# infnoise_edgecon.net
KiCad netlist of a schematic drawn in EAGLE
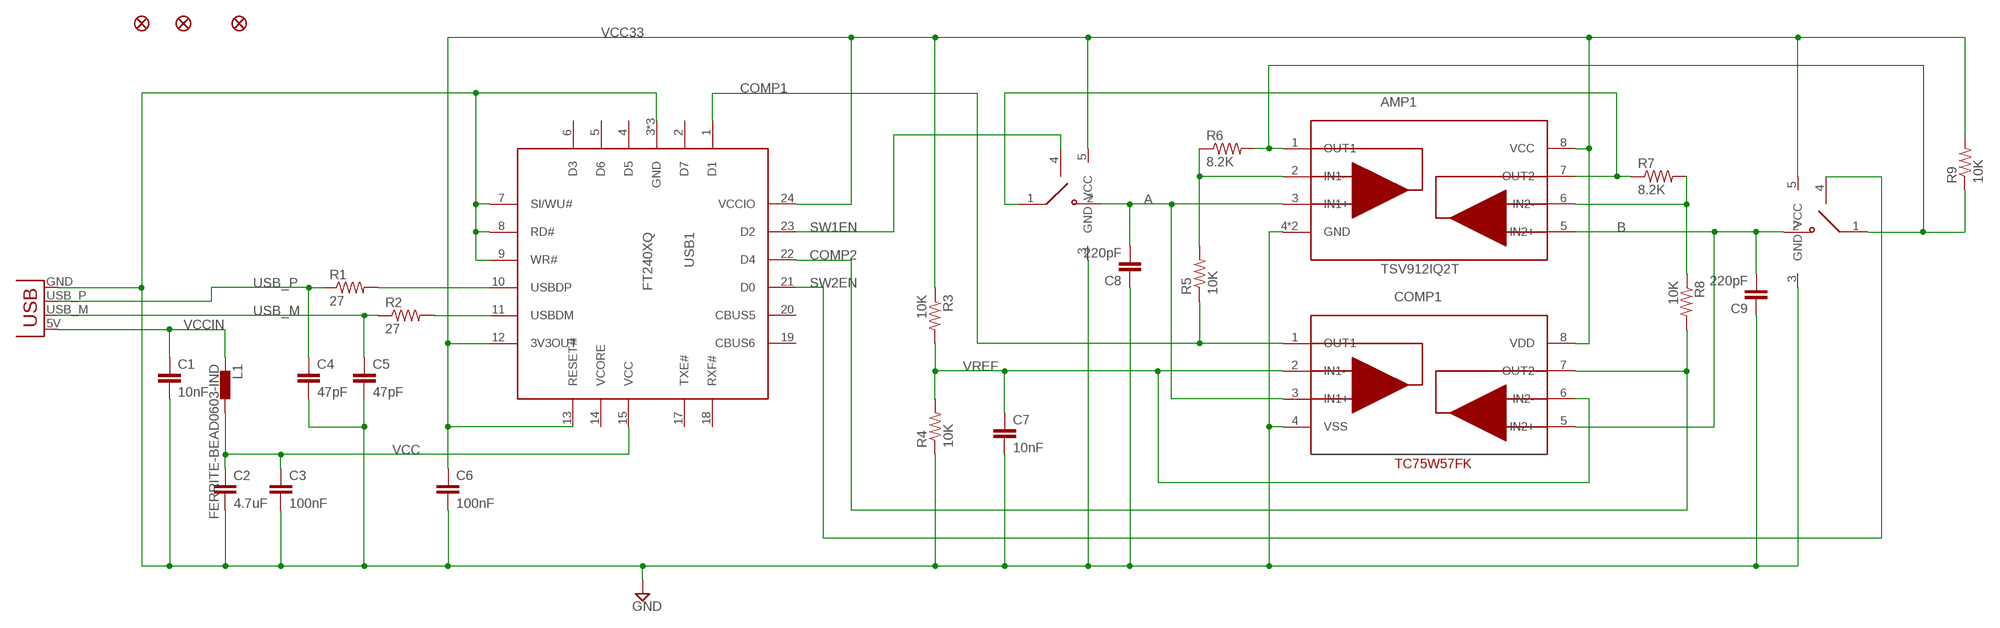
[diagram p0: schematic, sheet 1]

(export (version "E")
  (design (tool "Eeschema 10.0.6"))
  (components
    (comp (ref "AMP1")
      (value "TSV912IQ2T")
      (footprint "eagle-import:DFN8-2X3")
      (libsource (lib "eagle-import") (part "TSV912IQ2T"))
    )
    (comp (ref "C1")
      (value "10nF")
      (footprint "eagle-import:0603-CAP")
      (libsource (lib "eagle-import") (part "CAP0603-CAP"))
    )
    (comp (ref "C2")
      (value "4.7uF")
      (footprint "eagle-import:0603-CAP")
      (libsource (lib "eagle-import") (part "CAP0603-CAP"))
    )
    (comp (ref "C3")
      (value "100nF")
      (footprint "eagle-import:0603-CAP")
      (libsource (lib "eagle-import") (part "CAP0603-CAP"))
    )
    (comp (ref "C4")
      (value "47pF")
      (footprint "eagle-import:0603-CAP")
      (libsource (lib "eagle-import") (part "CAP0603-CAP"))
    )
    (comp (ref "C5")
      (value "47pF")
      (footprint "eagle-import:0603-CAP")
      (libsource (lib "eagle-import") (part "CAP0603-CAP"))
    )
    (comp (ref "C6")
      (value "100nF")
      (footprint "eagle-import:0603-CAP")
      (libsource (lib "eagle-import") (part "CAP0603-CAP"))
    )
    (comp (ref "C7")
      (value "10nF")
      (footprint "eagle-import:0603-CAP")
      (libsource (lib "eagle-import") (part "CAP0603-CAP"))
    )
    (comp (ref "C8")
      (value "220pF")
      (footprint "eagle-import:0603-CAP")
      (libsource (lib "eagle-import") (part "CAP0603-CAP"))
    )
    (comp (ref "C9")
      (value "220pF")
      (footprint "eagle-import:0603-CAP")
      (libsource (lib "eagle-import") (part "CAP0603-CAP"))
    )
    (comp (ref "COMP1")
      (value "TC75W57FK")
      (footprint "eagle-import:SSOP8-P-0.50A")
      (libsource (lib "eagle-import") (part "TC75W57FK"))
    )
    (comp (ref "FID1")
      (value "FIDUCIALUFIDUCIAL")
      (footprint "eagle-import:MICRO-FIDUCIAL")
      (libsource (lib "eagle-import") (part "FIDUCIALUFIDUCIAL"))
    )
    (comp (ref "FID2")
      (value "FIDUCIALUFIDUCIAL")
      (footprint "eagle-import:MICRO-FIDUCIAL")
      (libsource (lib "eagle-import") (part "FIDUCIALUFIDUCIAL"))
    )
    (comp (ref "FID3")
      (value "FIDUCIALUFIDUCIAL")
      (footprint "eagle-import:MICRO-FIDUCIAL")
      (libsource (lib "eagle-import") (part "FIDUCIALUFIDUCIAL"))
    )
    (comp (ref "L1")
      (value "FERRITE-BEAD0603-IND")
      (footprint "eagle-import:0603-IND")
      (libsource (lib "eagle-import") (part "FERRITE-BEAD0603-IND"))
    )
    (comp (ref "R1")
      (value "27")
      (footprint "eagle-import:0603-RES")
      (libsource (lib "eagle-import") (part "RESISTOR0603-RES"))
    )
    (comp (ref "R2")
      (value "27")
      (footprint "eagle-import:0603-RES")
      (libsource (lib "eagle-import") (part "RESISTOR0603-RES"))
    )
    (comp (ref "R3")
      (value "10K")
      (footprint "eagle-import:0603-RES")
      (libsource (lib "eagle-import") (part "RESISTOR0603-RES"))
    )
    (comp (ref "R4")
      (value "10K")
      (footprint "eagle-import:0603-RES")
      (libsource (lib "eagle-import") (part "RESISTOR0603-RES"))
    )
    (comp (ref "R5")
      (value "10K")
      (footprint "eagle-import:0603-RES")
      (libsource (lib "eagle-import") (part "RESISTOR0603-RES"))
    )
    (comp (ref "R6")
      (value "8.2K")
      (footprint "eagle-import:0603-RES")
      (libsource (lib "eagle-import") (part "RESISTOR0603-RES"))
    )
    (comp (ref "R7")
      (value "8.2K")
      (footprint "eagle-import:0603-RES")
      (libsource (lib "eagle-import") (part "RESISTOR0603-RES"))
    )
    (comp (ref "R8")
      (value "10K")
      (footprint "eagle-import:0603-RES")
      (libsource (lib "eagle-import") (part "RESISTOR0603-RES"))
    )
    (comp (ref "R9")
      (value "10K")
      (footprint "eagle-import:0603-RES")
      (libsource (lib "eagle-import") (part "RESISTOR0603-RES"))
    )
    (comp (ref "SW1")
      (value "MC74VHC1G66DFT1G")
      (footprint "eagle-import:SC70-5L")
      (libsource (lib "eagle-import") (part "MC74VHC1G66DFT1G"))
    )
    (comp (ref "SW2")
      (value "MC74VHC1G66DFT1G")
      (footprint "eagle-import:SC70-5L")
      (libsource (lib "eagle-import") (part "MC74VHC1G66DFT1G"))
    )
    (comp (ref "USB1")
      (value "FT240XQ")
      (footprint "eagle-import:QFN24-4X4")
      (libsource (lib "eagle-import") (part "FT240XQ"))
    )
    (comp (ref "X1")
      (value "USB")
      (footprint "eagle-import:USB-A-PCB")
      (libsource (lib "eagle-import") (part "USB"))
    )
  )
  (nets
    (net (code "1") (name "/A") (class "Default")
      (node (ref "AMP1") (pin "3") (pinfunction "IN1+_3") (pintype "bidirectional"))
      (node (ref "C8") (pin "2") (pinfunction "2_2") (pintype "passive"))
      (node (ref "COMP1") (pin "3") (pinfunction "IN1+_3") (pintype "bidirectional"))
      (node (ref "SW1") (pin "2") (pinfunction "NO_2") (pintype "bidirectional"))
    )
    (net (code "2") (name "/B") (class "Default")
      (node (ref "AMP1") (pin "5") (pinfunction "IN2+_5") (pintype "bidirectional"))
      (node (ref "C9") (pin "2") (pinfunction "2_2") (pintype "passive"))
      (node (ref "COMP1") (pin "5") (pinfunction "IN2+_5") (pintype "bidirectional"))
      (node (ref "SW2") (pin "2") (pinfunction "NO_2") (pintype "bidirectional"))
    )
    (net (code "3") (name "/COMP1") (class "Default")
      (node (ref "COMP1") (pin "1") (pinfunction "OUT1_1") (pintype "bidirectional"))
      (node (ref "R5") (pin "1") (pinfunction "1_1") (pintype "passive"))
      (node (ref "USB1") (pin "1") (pinfunction "D1_1") (pintype "bidirectional"))
    )
    (net (code "4") (name "/COMP2") (class "Default")
      (node (ref "COMP1") (pin "7") (pinfunction "OUT2_7") (pintype "bidirectional"))
      (node (ref "R8") (pin "2") (pinfunction "2_2") (pintype "passive"))
      (node (ref "USB1") (pin "22") (pinfunction "D4_22") (pintype "bidirectional"))
    )
    (net (code "5") (name "/SW1EN") (class "Default")
      (node (ref "SW1") (pin "4") (pinfunction "IN_4") (pintype "bidirectional"))
      (node (ref "USB1") (pin "23") (pinfunction "D2_23") (pintype "bidirectional"))
    )
    (net (code "6") (name "/SW2EN") (class "Default")
      (node (ref "SW2") (pin "4") (pinfunction "IN_4") (pintype "bidirectional"))
      (node (ref "USB1") (pin "21") (pinfunction "D0_21") (pintype "bidirectional"))
    )
    (net (code "7") (name "/USB_M") (class "Default")
      (node (ref "C5") (pin "1") (pinfunction "1_1") (pintype "passive"))
      (node (ref "R2") (pin "1") (pinfunction "1_1") (pintype "passive"))
      (node (ref "X1") (pin "USB_M") (pinfunction "D-_USB_M") (pintype "bidirectional"))
    )
    (net (code "8") (name "/USB_P") (class "Default")
      (node (ref "C4") (pin "1") (pinfunction "1_1") (pintype "passive"))
      (node (ref "R1") (pin "1") (pinfunction "1_1") (pintype "passive"))
      (node (ref "X1") (pin "USB_P") (pinfunction "D+_USB_P") (pintype "bidirectional"))
    )
    (net (code "9") (name "/VCC") (class "Default")
      (node (ref "C2") (pin "1") (pinfunction "1_1") (pintype "passive"))
      (node (ref "C3") (pin "1") (pinfunction "1_1") (pintype "passive"))
      (node (ref "L1") (pin "2") (pinfunction "2_2") (pintype "passive"))
      (node (ref "USB1") (pin "15") (pinfunction "VCC_15") (pintype "bidirectional"))
    )
    (net (code "10") (name "/VCC33") (class "Default")
      (node (ref "AMP1") (pin "8") (pinfunction "VCC_8") (pintype "bidirectional"))
      (node (ref "C6") (pin "1") (pinfunction "1_1") (pintype "passive"))
      (node (ref "COMP1") (pin "8") (pinfunction "VDD_8") (pintype "bidirectional"))
      (node (ref "R3") (pin "1") (pinfunction "1_1") (pintype "passive"))
      (node (ref "R9") (pin "2") (pinfunction "2_2") (pintype "passive"))
      (node (ref "SW1") (pin "5") (pinfunction "VCC_5") (pintype "bidirectional"))
      (node (ref "SW2") (pin "5") (pinfunction "VCC_5") (pintype "bidirectional"))
      (node (ref "USB1") (pin "12") (pinfunction "3V3OUT_12") (pintype "bidirectional"))
      (node (ref "USB1") (pin "13") (pinfunction "RESET#_13") (pintype "bidirectional"))
      (node (ref "USB1") (pin "24") (pinfunction "VCCIO_24") (pintype "bidirectional"))
    )
    (net (code "11") (name "/VCCIN") (class "Default")
      (node (ref "C1") (pin "1") (pinfunction "1_1") (pintype "passive"))
      (node (ref "L1") (pin "1") (pinfunction "1_1") (pintype "passive"))
      (node (ref "X1") (pin "5V") (pinfunction "VCC_5V") (pintype "bidirectional"))
    )
    (net (code "12") (name "/VREF") (class "Default")
      (node (ref "C7") (pin "1") (pinfunction "1_1") (pintype "passive"))
      (node (ref "COMP1") (pin "2") (pinfunction "IN1-_2") (pintype "bidirectional"))
      (node (ref "COMP1") (pin "6") (pinfunction "IN2-_6") (pintype "bidirectional"))
      (node (ref "R3") (pin "2") (pinfunction "2_2") (pintype "passive"))
      (node (ref "R4") (pin "2") (pinfunction "2_2") (pintype "passive"))
    )
    (net (code "13") (name "GND") (class "Default")
      (node (ref "AMP1") (pin "4") (pinfunction "GND_4") (pintype "bidirectional"))
      (node (ref "AMP1") (pin "EXP") (pinfunction "GND_EXP") (pintype "bidirectional"))
      (node (ref "C1") (pin "2") (pinfunction "2_2") (pintype "passive"))
      (node (ref "C2") (pin "2") (pinfunction "2_2") (pintype "passive"))
      (node (ref "C3") (pin "2") (pinfunction "2_2") (pintype "passive"))
      (node (ref "C4") (pin "2") (pinfunction "2_2") (pintype "passive"))
      (node (ref "C5") (pin "2") (pinfunction "2_2") (pintype "passive"))
      (node (ref "C6") (pin "2") (pinfunction "2_2") (pintype "passive"))
      (node (ref "C7") (pin "2") (pinfunction "2_2") (pintype "passive"))
      (node (ref "C8") (pin "1") (pinfunction "1_1") (pintype "passive"))
      (node (ref "C9") (pin "1") (pinfunction "1_1") (pintype "passive"))
      (node (ref "COMP1") (pin "4") (pinfunction "VSS_4") (pintype "bidirectional"))
      (node (ref "R4") (pin "1") (pinfunction "1_1") (pintype "passive"))
      (node (ref "SW1") (pin "3") (pinfunction "GND_3") (pintype "bidirectional"))
      (node (ref "SW2") (pin "3") (pinfunction "GND_3") (pintype "bidirectional"))
      (node (ref "USB1") (pin "16") (pinfunction "GND_16") (pintype "bidirectional"))
      (node (ref "USB1") (pin "3") (pinfunction "GND_3") (pintype "bidirectional"))
      (node (ref "USB1") (pin "7") (pinfunction "SI/WU#_7") (pintype "bidirectional"))
      (node (ref "USB1") (pin "8") (pinfunction "RD#_8") (pintype "bidirectional"))
      (node (ref "USB1") (pin "9") (pinfunction "WR#_9") (pintype "bidirectional"))
      (node (ref "USB1") (pin "EXP") (pinfunction "GND_EXP") (pintype "bidirectional"))
      (node (ref "X1") (pin "GND") (pinfunction "GND_GND") (pintype "bidirectional"))
    )
    (net (code "14") (name "Net-(AMP1-IN1-)") (class "Default")
      (node (ref "AMP1") (pin "2") (pinfunction "IN1-_2") (pintype "bidirectional"))
      (node (ref "R5") (pin "2") (pinfunction "2_2") (pintype "passive"))
      (node (ref "R6") (pin "1") (pinfunction "1_1") (pintype "passive"))
    )
    (net (code "15") (name "Net-(AMP1-IN2-)") (class "Default")
      (node (ref "AMP1") (pin "6") (pinfunction "IN2-_6") (pintype "bidirectional"))
      (node (ref "R7") (pin "2") (pinfunction "2_2") (pintype "passive"))
      (node (ref "R8") (pin "1") (pinfunction "1_1") (pintype "passive"))
    )
    (net (code "16") (name "Net-(AMP1-OUT1)") (class "Default")
      (node (ref "AMP1") (pin "1") (pinfunction "OUT1_1") (pintype "bidirectional"))
      (node (ref "R6") (pin "2") (pinfunction "2_2") (pintype "passive"))
      (node (ref "R9") (pin "1") (pinfunction "1_1") (pintype "passive"))
      (node (ref "SW2") (pin "1") (pinfunction "COM_1") (pintype "bidirectional"))
    )
    (net (code "17") (name "Net-(AMP1-OUT2)") (class "Default")
      (node (ref "AMP1") (pin "7") (pinfunction "OUT2_7") (pintype "bidirectional"))
      (node (ref "R7") (pin "1") (pinfunction "1_1") (pintype "passive"))
      (node (ref "SW1") (pin "1") (pinfunction "COM_1") (pintype "bidirectional"))
    )
    (net (code "18") (name "Net-(USB1-USBDM)") (class "Default")
      (node (ref "R2") (pin "2") (pinfunction "2_2") (pintype "passive"))
      (node (ref "USB1") (pin "11") (pinfunction "USBDM_11") (pintype "bidirectional"))
    )
    (net (code "19") (name "Net-(USB1-USBDP)") (class "Default")
      (node (ref "R1") (pin "2") (pinfunction "2_2") (pintype "passive"))
      (node (ref "USB1") (pin "10") (pinfunction "USBDP_10") (pintype "bidirectional"))
    )
    (net (code "20") (name "unconnected-(USB1-CBUS5-Pad20)") (class "Default")
      (node (ref "USB1") (pin "20") (pinfunction "CBUS5_20") (pintype "bidirectional"))
    )
    (net (code "21") (name "unconnected-(USB1-CBUS6-Pad19)") (class "Default")
      (node (ref "USB1") (pin "19") (pinfunction "CBUS6_19") (pintype "bidirectional"))
    )
    (net (code "22") (name "unconnected-(USB1-D3-Pad6)") (class "Default")
      (node (ref "USB1") (pin "6") (pinfunction "D3_6") (pintype "bidirectional"))
    )
    (net (code "23") (name "unconnected-(USB1-D5-Pad4)") (class "Default")
      (node (ref "USB1") (pin "4") (pinfunction "D5_4") (pintype "bidirectional"))
    )
    (net (code "24") (name "unconnected-(USB1-D6-Pad5)") (class "Default")
      (node (ref "USB1") (pin "5") (pinfunction "D6_5") (pintype "bidirectional"))
    )
    (net (code "25") (name "unconnected-(USB1-D7-Pad2)") (class "Default")
      (node (ref "USB1") (pin "2") (pinfunction "D7_2") (pintype "bidirectional"))
    )
    (net (code "26") (name "unconnected-(USB1-RXF#-Pad18)") (class "Default")
      (node (ref "USB1") (pin "18") (pinfunction "RXF#_18") (pintype "bidirectional"))
    )
    (net (code "27") (name "unconnected-(USB1-TXE#-Pad17)") (class "Default")
      (node (ref "USB1") (pin "17") (pinfunction "TXE#_17") (pintype "bidirectional"))
    )
    (net (code "28") (name "unconnected-(USB1-VCORE-Pad14)") (class "Default")
      (node (ref "USB1") (pin "14") (pinfunction "VCORE_14") (pintype "bidirectional"))
    )
  )
)
